# 09-LED.net
KiCad netlist of a schematic drawn in Altium Designer
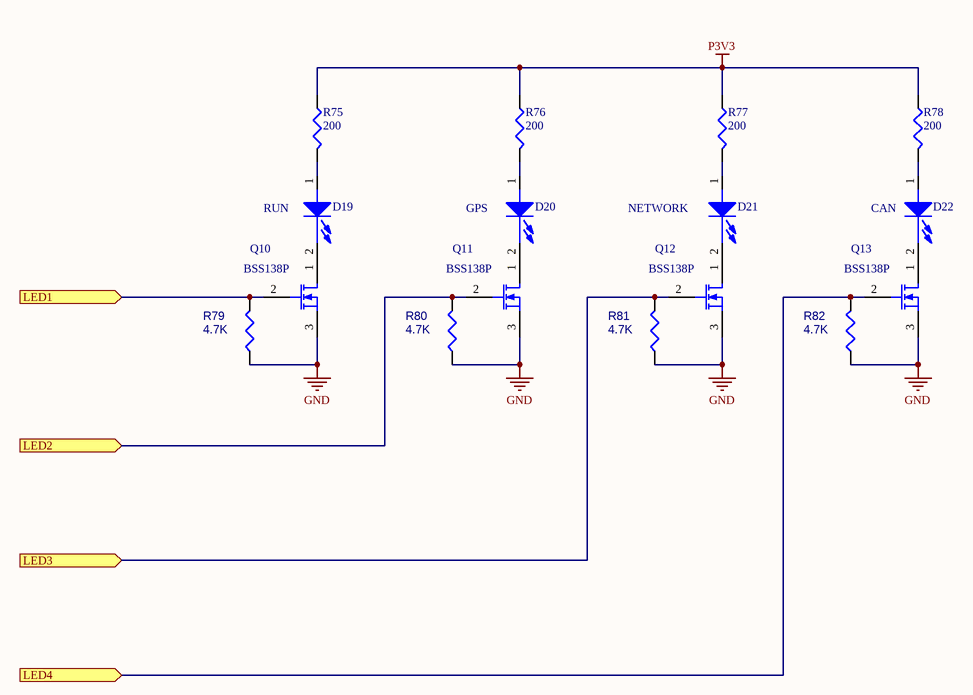
[diagram p0: 09-LED.SchDoc]

(export (version "E")
  (design (tool "Eeschema 10.0.6"))
  (components
    (comp (ref "D19") (value "LED GREEN") (footprint "LED-3MM") (libsource (lib "*") (part "LN01401_1")))
    (comp (ref "D20") (value "LED GREEN") (footprint "LED-3MM") (libsource (lib "*") (part "LN01401_1")))
    (comp (ref "D21") (value "LED GREEN") (footprint "LED-3MM") (libsource (lib "*") (part "LN01401_1")))
    (comp (ref "D22") (value "LED GREEN") (footprint "LED-3MM") (libsource (lib "*") (part "LN01401_1")))
    (comp (ref "Q10")
      (value "BSS138P")
      (footprint "NPN")
      (description "N-Channel MOSFET")
      (fields (field (name "PUBLISHER") "Altium Limited"))
      (libsource (lib "Miscellaneous Devices") (part "MOSFET-N"))
    )
    (comp (ref "Q11")
      (value "BSS138P")
      (footprint "NPN")
      (description "N-Channel MOSFET")
      (fields (field (name "PUBLISHER") "Altium Limited"))
      (libsource (lib "Miscellaneous Devices") (part "MOSFET-N"))
    )
    (comp (ref "Q12")
      (value "BSS138P")
      (footprint "NPN")
      (description "N-Channel MOSFET")
      (fields (field (name "PUBLISHER") "Altium Limited"))
      (libsource (lib "Miscellaneous Devices") (part "MOSFET-N"))
    )
    (comp (ref "Q13")
      (value "BSS138P")
      (footprint "NPN")
      (description "N-Channel MOSFET")
      (fields (field (name "PUBLISHER") "Altium Limited"))
      (libsource (lib "Miscellaneous Devices") (part "MOSFET-N"))
    )
    (comp (ref "R75") (value "200") (footprint "0402") (libsource (lib "*") (part "CR16-1003FM")))
    (comp (ref "R76") (value "200") (footprint "0402") (libsource (lib "*") (part "CR16-1003FM")))
    (comp (ref "R77") (value "200") (footprint "0402") (libsource (lib "*") (part "CR16-1003FM")))
    (comp (ref "R78") (value "200") (footprint "0402") (libsource (lib "*") (part "CR16-1003FM")))
    (comp (ref "R79") (value "4.7K") (libsource (lib "*") (part "R")))
    (comp (ref "R80") (value "4.7K") (libsource (lib "*") (part "R")))
    (comp (ref "R81") (value "4.7K") (libsource (lib "*") (part "R")))
    (comp (ref "R82") (value "4.7K") (libsource (lib "*") (part "R")))
  )
  (nets
    (net (code "1") (name "/LED1") (class "Default")
      (node (ref "Q10") (pin "2") (pinfunction "G_2") (pintype "passive"))
      (node (ref "R79") (pin "2") (pinfunction "2_2") (pintype "passive"))
    )
    (net (code "2") (name "/LED2") (class "Default")
      (node (ref "Q11") (pin "2") (pinfunction "G_2") (pintype "passive"))
      (node (ref "R80") (pin "2") (pinfunction "2_2") (pintype "passive"))
    )
    (net (code "3") (name "/LED3") (class "Default")
      (node (ref "Q12") (pin "2") (pinfunction "G_2") (pintype "passive"))
      (node (ref "R81") (pin "2") (pinfunction "2_2") (pintype "passive"))
    )
    (net (code "4") (name "/LED4") (class "Default")
      (node (ref "Q13") (pin "2") (pinfunction "G_2") (pintype "passive"))
      (node (ref "R82") (pin "2") (pinfunction "2_2") (pintype "passive"))
    )
    (net (code "5") (name "GND") (class "Default")
      (node (ref "Q10") (pin "3") (pinfunction "S_3") (pintype "passive"))
      (node (ref "Q11") (pin "3") (pinfunction "S_3") (pintype "passive"))
      (node (ref "Q12") (pin "3") (pinfunction "S_3") (pintype "passive"))
      (node (ref "Q13") (pin "3") (pinfunction "S_3") (pintype "passive"))
      (node (ref "R79") (pin "1") (pinfunction "1_1") (pintype "passive"))
      (node (ref "R80") (pin "1") (pinfunction "1_1") (pintype "passive"))
      (node (ref "R81") (pin "1") (pinfunction "1_1") (pintype "passive"))
      (node (ref "R82") (pin "1") (pinfunction "1_1") (pintype "passive"))
    )
    (net (code "6") (name "Net-(D19-ANODE)") (class "Default")
      (node (ref "D19") (pin "1") (pinfunction "ANODE_1") (pintype "passive"))
      (node (ref "R75") (pin "2") (pinfunction "2_2") (pintype "passive"))
    )
    (net (code "7") (name "Net-(D19-CATHODE)") (class "Default")
      (node (ref "D19") (pin "2") (pinfunction "CATHODE_2") (pintype "passive"))
      (node (ref "Q10") (pin "1") (pinfunction "D_1") (pintype "passive"))
    )
    (net (code "8") (name "Net-(D20-ANODE)") (class "Default")
      (node (ref "D20") (pin "1") (pinfunction "ANODE_1") (pintype "passive"))
      (node (ref "R76") (pin "2") (pinfunction "2_2") (pintype "passive"))
    )
    (net (code "9") (name "Net-(D20-CATHODE)") (class "Default")
      (node (ref "D20") (pin "2") (pinfunction "CATHODE_2") (pintype "passive"))
      (node (ref "Q11") (pin "1") (pinfunction "D_1") (pintype "passive"))
    )
    (net (code "10") (name "Net-(D21-ANODE)") (class "Default")
      (node (ref "D21") (pin "1") (pinfunction "ANODE_1") (pintype "passive"))
      (node (ref "R77") (pin "2") (pinfunction "2_2") (pintype "passive"))
    )
    (net (code "11") (name "Net-(D21-CATHODE)") (class "Default")
      (node (ref "D21") (pin "2") (pinfunction "CATHODE_2") (pintype "passive"))
      (node (ref "Q12") (pin "1") (pinfunction "D_1") (pintype "passive"))
    )
    (net (code "12") (name "Net-(D22-ANODE)") (class "Default")
      (node (ref "D22") (pin "1") (pinfunction "ANODE_1") (pintype "passive"))
      (node (ref "R78") (pin "2") (pinfunction "2_2") (pintype "passive"))
    )
    (net (code "13") (name "Net-(D22-CATHODE)") (class "Default")
      (node (ref "D22") (pin "2") (pinfunction "CATHODE_2") (pintype "passive"))
      (node (ref "Q13") (pin "1") (pinfunction "D_1") (pintype "passive"))
    )
    (net (code "14") (name "P3V3") (class "Default")
      (node (ref "R75") (pin "1") (pinfunction "1_1") (pintype "passive"))
      (node (ref "R76") (pin "1") (pinfunction "1_1") (pintype "passive"))
      (node (ref "R77") (pin "1") (pinfunction "1_1") (pintype "passive"))
      (node (ref "R78") (pin "1") (pinfunction "1_1") (pintype "passive"))
    )
  )
)
